# magloop_ad8129.net
KiCad netlist of a schematic drawn in EAGLE
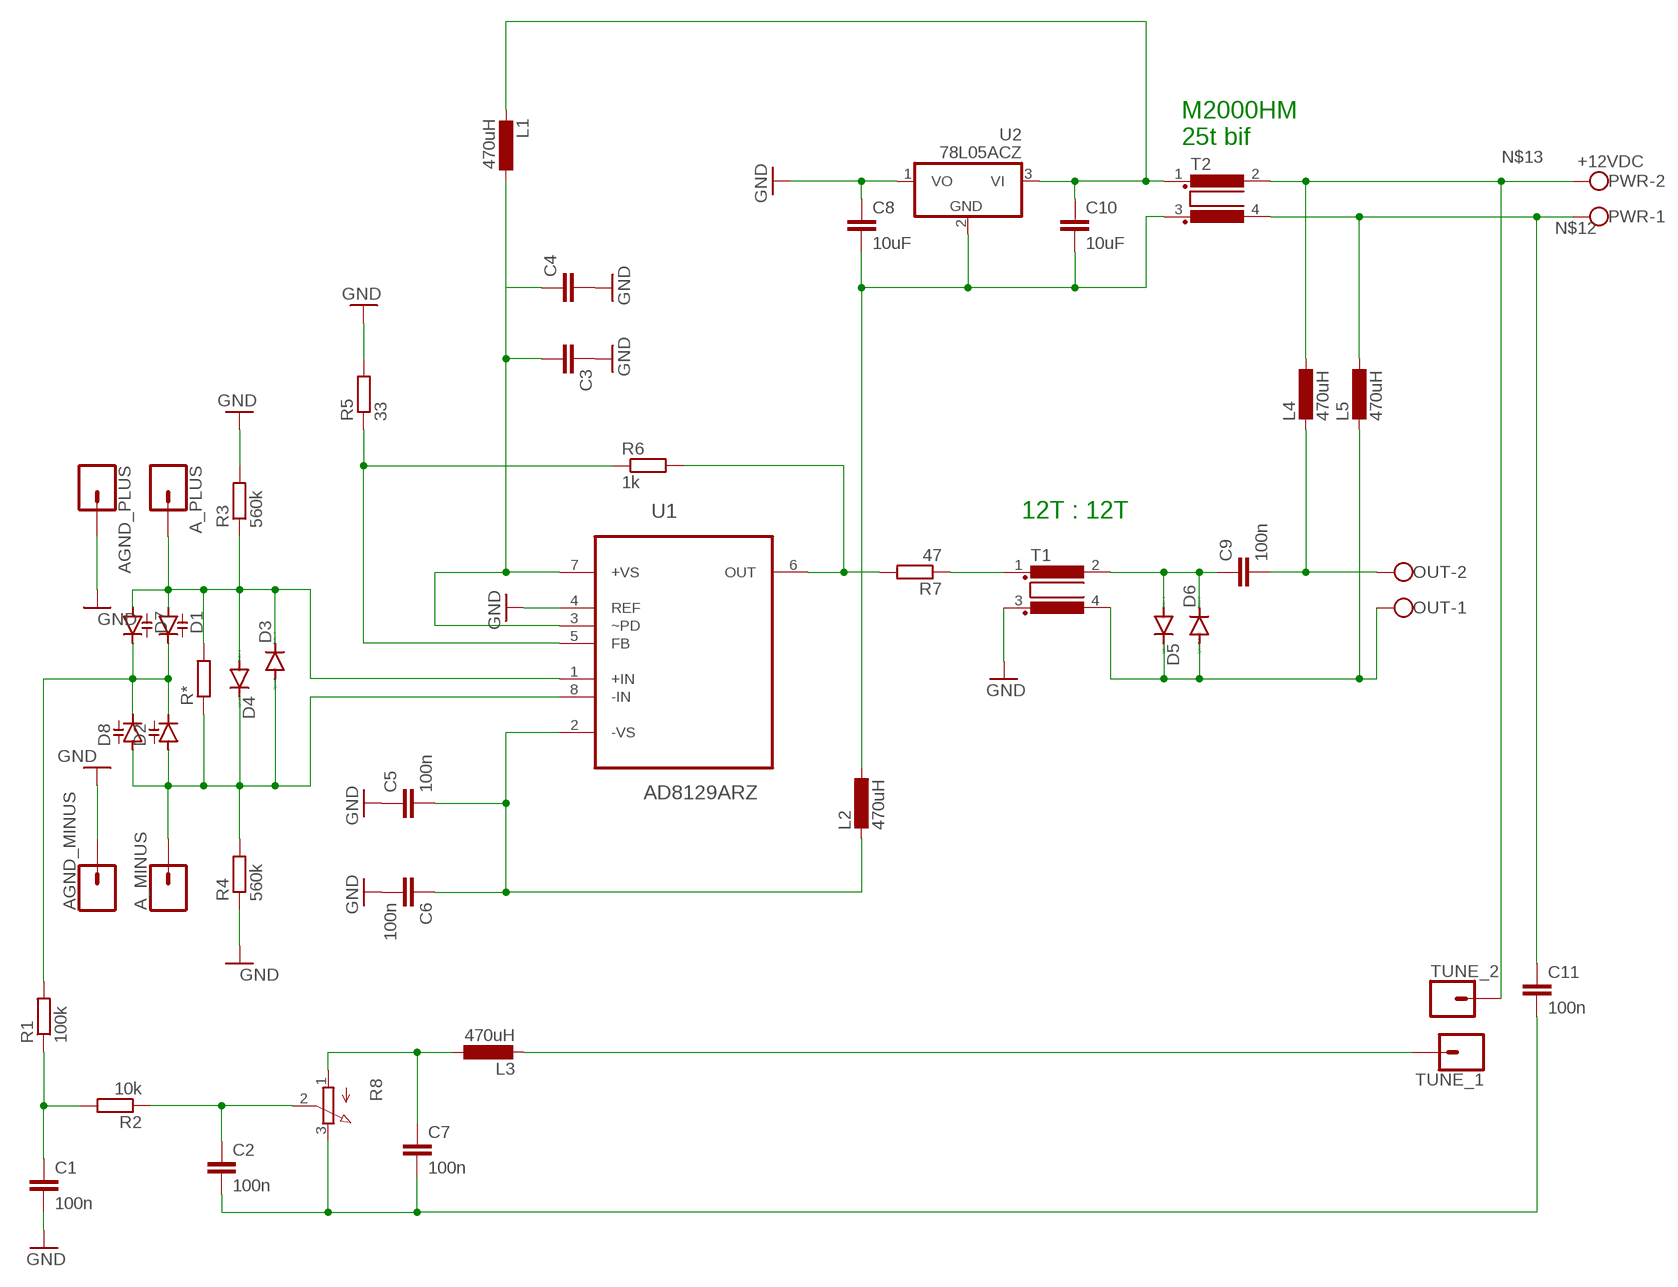
[diagram p0: schematic, sheet 1]

(export (version "E")
  (design (tool "Eeschema 10.0.6"))
  (components
    (comp (ref "AGND_MINUS")
      (value "CONN_01PTH_2MM")
      (footprint "eagle-import:1X01_2MM")
      (libsource (lib "eagle-import") (part "SparkFun-Connectors_CONN_01PTH_2MM"))
    )
    (comp (ref "AGND_PLUS")
      (value "CONN_01PTH_2MM")
      (footprint "eagle-import:1X01_2MM")
      (libsource (lib "eagle-import") (part "SparkFun-Connectors_CONN_01PTH_2MM"))
    )
    (comp (ref "A_MINUS")
      (value "CONN_01PTH_2MM")
      (footprint "eagle-import:1X01_2MM")
      (libsource (lib "eagle-import") (part "CONN_01PTH_2MM"))
    )
    (comp (ref "A_PLUS")
      (value "CONN_01PTH_2MM")
      (footprint "eagle-import:1X01_2MM")
      (libsource (lib "eagle-import") (part "CONN_01PTH_2MM"))
    )
    (comp (ref "C1")
      (value "100n")
      (footprint "eagle-import:C1206")
      (libsource (lib "eagle-import") (part "C-EUC1206"))
    )
    (comp (ref "C2")
      (value "100n")
      (footprint "eagle-import:C1206")
      (libsource (lib "eagle-import") (part "C-EUC1206"))
    )
    (comp (ref "C3")
      (value "C-EUC1206K")
      (footprint "eagle-import:C1206K")
      (libsource (lib "eagle-import") (part "C-EUC1206K"))
    )
    (comp (ref "C4")
      (value "C-EUC1206K")
      (footprint "eagle-import:C1206K")
      (libsource (lib "eagle-import") (part "C-EUC1206K"))
    )
    (comp (ref "C5")
      (value "100n")
      (footprint "eagle-import:C1206K")
      (libsource (lib "eagle-import") (part "C-EUC1206K"))
    )
    (comp (ref "C6")
      (value "100n")
      (footprint "eagle-import:C1206K")
      (libsource (lib "eagle-import") (part "C-EUC1206K"))
    )
    (comp (ref "C7")
      (value "100n")
      (footprint "eagle-import:C1206")
      (libsource (lib "eagle-import") (part "C-EUC1206"))
    )
    (comp (ref "C8")
      (value "10uF")
      (footprint "eagle-import:C1206K")
      (libsource (lib "eagle-import") (part "C-EUC1206K"))
    )
    (comp (ref "C9")
      (value "100n")
      (footprint "eagle-import:C1206")
      (libsource (lib "eagle-import") (part "C-EUC1206"))
    )
    (comp (ref "C10")
      (value "10uF")
      (footprint "eagle-import:C1206K")
      (libsource (lib "eagle-import") (part "C-EUC1206K"))
    )
    (comp (ref "C11")
      (value "100n")
      (footprint "eagle-import:C1206K")
      (libsource (lib "eagle-import") (part "C-EUC1206K"))
    )
    (comp (ref "D1")
      (value "1SV149")
      (footprint "eagle-import:SOT54H")
      (libsource (lib "eagle-import") (part "DIODE_CAPACITANCE-SOT54H"))
    )
    (comp (ref "D2")
      (value "1SV149")
      (footprint "eagle-import:SOT54H")
      (libsource (lib "eagle-import") (part "DIODE_CAPACITANCE-SOT54H"))
    )
    (comp (ref "D3")
      (value "LL4148")
      (footprint "eagle-import:SOD-123_MINI-SMA")
      (libsource (lib "eagle-import") (part "CGRM400-G1"))
    )
    (comp (ref "D4")
      (value "LL4148")
      (footprint "eagle-import:SOD-123_MINI-SMA")
      (libsource (lib "eagle-import") (part "CGRM400-G1"))
    )
    (comp (ref "D5")
      (value "CGRM4001-G")
      (footprint "eagle-import:SOD-123_MINI-SMA")
      (libsource (lib "eagle-import") (part "CGRM400-G1"))
    )
    (comp (ref "D6")
      (value "CGRM4001-G")
      (footprint "eagle-import:SOD-123_MINI-SMA")
      (libsource (lib "eagle-import") (part "CGRM400-G1"))
    )
    (comp (ref "D7")
      (value "1SV149")
      (footprint "eagle-import:SOT54H")
      (libsource (lib "eagle-import") (part "DIODE_CAPACITANCE-SOT54H"))
    )
    (comp (ref "D8")
      (value "1SV149")
      (footprint "eagle-import:SOT54H")
      (libsource (lib "eagle-import") (part "DIODE_CAPACITANCE-SOT54H"))
    )
    (comp (ref "L1")
      (value "470uH")
      (footprint "eagle-import:0207_10")
      (libsource (lib "eagle-import") (part "L-EU0207/10"))
    )
    (comp (ref "L2")
      (value "470uH")
      (footprint "eagle-import:0207_10")
      (libsource (lib "eagle-import") (part "L-EU0207/10"))
    )
    (comp (ref "L3")
      (value "470uH")
      (footprint "eagle-import:0207_10")
      (libsource (lib "eagle-import") (part "L-EU0207/10"))
    )
    (comp (ref "L4")
      (value "470uH")
      (footprint "eagle-import:0207_10")
      (libsource (lib "eagle-import") (part "L-EU0207/10"))
    )
    (comp (ref "L5")
      (value "470uH")
      (footprint "eagle-import:0207_10")
      (libsource (lib "eagle-import") (part "L-EU0207/10"))
    )
    (comp (ref "OUT")
      (value "W237-102")
      (footprint "eagle-import:W237-102")
      (fields (field (name "MPN") "237-102"))
      (libsource (lib "eagle-import") (part "W237-102"))
    )
    (comp (ref "PWR")
      (value "+12VDC")
      (footprint "eagle-import:W237-102")
      (fields (field (name "MPN") "237-102"))
      (libsource (lib "eagle-import") (part "W237-102"))
    )
    (comp (ref "R*")
      (value "R-EU_R1206")
      (footprint "eagle-import:R1206")
      (libsource (lib "eagle-import") (part "R-EU_R1206"))
    )
    (comp (ref "R1")
      (value "100k")
      (footprint "eagle-import:R1206")
      (libsource (lib "eagle-import") (part "R-EU_R1206"))
    )
    (comp (ref "R2")
      (value "10k")
      (footprint "eagle-import:R1206")
      (libsource (lib "eagle-import") (part "R-EU_R1206"))
    )
    (comp (ref "R3")
      (value "560k")
      (footprint "eagle-import:R1206")
      (libsource (lib "eagle-import") (part "R-EU_R1206"))
    )
    (comp (ref "R4")
      (value "560k")
      (footprint "eagle-import:R1206")
      (libsource (lib "eagle-import") (part "R-EU_R1206"))
    )
    (comp (ref "R5")
      (value "33")
      (footprint "eagle-import:R1206")
      (libsource (lib "eagle-import") (part "R-EU_R1206"))
    )
    (comp (ref "R6")
      (value "1k")
      (footprint "eagle-import:R1206")
      (libsource (lib "eagle-import") (part "R-EU_R1206"))
    )
    (comp (ref "R7")
      (value "47")
      (footprint "eagle-import:R1206")
      (libsource (lib "eagle-import") (part "R-EU_R1206"))
    )
    (comp (ref "R8")
      (value "3RP/1610N")
      (footprint "eagle-import:3RP_1610N")
      (libsource (lib "eagle-import") (part "3RP/1610N"))
    )
    (comp (ref "T1")
      (value "R1405UB1/2")
      (footprint "eagle-import:B1_2")
      (libsource (lib "eagle-import") (part "R1405UB1/2"))
    )
    (comp (ref "T2")
      (value "R1405UB1/2")
      (footprint "eagle-import:B1_2")
      (libsource (lib "eagle-import") (part "R1405UB1/2"))
    )
    (comp (ref "TUNE_1")
      (value "CONN_01OFFSET")
      (footprint "eagle-import:1X01_OFFSET")
      (libsource (lib "eagle-import") (part "CONN_01OFFSET"))
    )
    (comp (ref "TUNE_2")
      (value "CONN_01OFFSET")
      (footprint "eagle-import:1X01_OFFSET")
      (libsource (lib "eagle-import") (part "CONN_01OFFSET"))
    )
    (comp (ref "U1")
      (value "AD8129ARZ")
      (footprint "eagle-import:SOIC127P600X175-8N")
      (fields (field (name "MF") "Analog Devices"))
      (libsource (lib "eagle-import") (part "AD8129ARZ"))
    )
    (comp (ref "U2")
      (value "78L05ACZ")
      (footprint "eagle-import:TO-92")
      (fields (field (name "MF") "STMicroelectronics"))
      (libsource (lib "eagle-import") (part "78L05ACZ"))
    )
  )
  (nets
    (net (code "1") (name "/N$12") (class "Default")
      (node (ref "C11") (pin "1") (pinfunction "1_1") (pintype "passive"))
      (node (ref "L5") (pin "1") (pinfunction "1_1") (pintype "passive"))
      (node (ref "PWR") (pin "1") (pinfunction "KL_1") (pintype "passive"))
      (node (ref "T2") (pin "4") (pinfunction "4_4") (pintype "passive"))
    )
    (net (code "2") (name "/N$13") (class "Default")
      (node (ref "L4") (pin "1") (pinfunction "1_1") (pintype "passive"))
      (node (ref "PWR") (pin "2") (pinfunction "KL_2") (pintype "passive"))
      (node (ref "T2") (pin "2") (pinfunction "2_2") (pintype "passive"))
      (node (ref "TUNE_2") (pin "1") (pinfunction "1_1") (pintype "passive"))
    )
    (net (code "3") (name "GND") (class "Default")
      (node (ref "AGND_MINUS") (pin "1") (pinfunction "1_1") (pintype "passive"))
      (node (ref "AGND_PLUS") (pin "1") (pinfunction "1_1") (pintype "passive"))
      (node (ref "C1") (pin "2") (pinfunction "2_2") (pintype "passive"))
      (node (ref "C3") (pin "1") (pinfunction "1_1") (pintype "passive"))
      (node (ref "C4") (pin "2") (pinfunction "2_2") (pintype "passive"))
      (node (ref "C5") (pin "1") (pinfunction "1_1") (pintype "passive"))
      (node (ref "C6") (pin "2") (pinfunction "2_2") (pintype "passive"))
      (node (ref "C8") (pin "1") (pinfunction "1_1") (pintype "passive"))
      (node (ref "R3") (pin "2") (pinfunction "2_2") (pintype "passive"))
      (node (ref "R4") (pin "1") (pinfunction "1_1") (pintype "passive"))
      (node (ref "R5") (pin "2") (pinfunction "2_2") (pintype "passive"))
      (node (ref "T1") (pin "3") (pinfunction "3_3") (pintype "passive"))
      (node (ref "U1") (pin "4") (pinfunction "REF_4") (pintype "input"))
      (node (ref "U2") (pin "1") (pinfunction "VO_1") (pintype "passive"))
    )
    (net (code "4") (name "Net-(C1-Pad1)") (class "Default")
      (node (ref "C1") (pin "1") (pinfunction "1_1") (pintype "passive"))
      (node (ref "R1") (pin "1") (pinfunction "1_1") (pintype "passive"))
      (node (ref "R2") (pin "2") (pinfunction "2_2") (pintype "passive"))
    )
    (net (code "5") (name "Net-(C9-Pad1)") (class "Default")
      (node (ref "C9") (pin "1") (pinfunction "1_1") (pintype "passive"))
      (node (ref "D5") (pin "A") (pinfunction "A_A") (pintype "passive"))
      (node (ref "D6") (pin "C") (pinfunction "C_C") (pintype "passive"))
      (node (ref "T1") (pin "2") (pinfunction "2_2") (pintype "passive"))
    )
    (net (code "6") (name "Net-(D1-PadC)") (class "Default")
      (node (ref "D1") (pin "C") (pinfunction "C_C") (pintype "passive"))
      (node (ref "D2") (pin "C") (pinfunction "C_C") (pintype "passive"))
      (node (ref "D7") (pin "C") (pinfunction "C_C") (pintype "passive"))
      (node (ref "D8") (pin "C") (pinfunction "C_C") (pintype "passive"))
      (node (ref "R1") (pin "2") (pinfunction "2_2") (pintype "passive"))
    )
    (net (code "7") (name "Net-(L3-Pad2)") (class "Default")
      (node (ref "L3") (pin "2") (pinfunction "2_2") (pintype "passive"))
      (node (ref "TUNE_1") (pin "1") (pinfunction "1_1") (pintype "passive"))
    )
    (net (code "8") (name "Net-(OUTA-KL)") (class "Default")
      (node (ref "D5") (pin "C") (pinfunction "C_C") (pintype "passive"))
      (node (ref "D6") (pin "A") (pinfunction "A_A") (pintype "passive"))
      (node (ref "L5") (pin "2") (pinfunction "2_2") (pintype "passive"))
      (node (ref "OUT") (pin "1") (pinfunction "KL_1") (pintype "passive"))
      (node (ref "T1") (pin "4") (pinfunction "4_4") (pintype "passive"))
    )
    (net (code "9") (name "Net-(OUTB-KL)") (class "Default")
      (node (ref "C9") (pin "2") (pinfunction "2_2") (pintype "passive"))
      (node (ref "L4") (pin "2") (pinfunction "2_2") (pintype "passive"))
      (node (ref "OUT") (pin "2") (pinfunction "KL_2") (pintype "passive"))
    )
    (net (code "10") (name "Net-(R7-Pad1)") (class "Default")
      (node (ref "R7") (pin "1") (pinfunction "1_1") (pintype "passive"))
      (node (ref "T1") (pin "1") (pinfunction "1_1") (pintype "passive"))
    )
    (net (code "11") (name "Net-(R8-A)") (class "Default")
      (node (ref "C7") (pin "1") (pinfunction "1_1") (pintype "passive"))
      (node (ref "L3") (pin "1") (pinfunction "1_1") (pintype "passive"))
      (node (ref "R8") (pin "1") (pinfunction "A_1") (pintype "passive"))
    )
    (net (code "12") (name "Net-(R8-E)") (class "Default")
      (node (ref "C11") (pin "2") (pinfunction "2_2") (pintype "passive"))
      (node (ref "C2") (pin "2") (pinfunction "2_2") (pintype "passive"))
      (node (ref "C7") (pin "2") (pinfunction "2_2") (pintype "passive"))
      (node (ref "R8") (pin "3") (pinfunction "E_3") (pintype "passive"))
    )
    (net (code "13") (name "Net-(R8-S)") (class "Default")
      (node (ref "C2") (pin "1") (pinfunction "1_1") (pintype "passive"))
      (node (ref "R2") (pin "1") (pinfunction "1_1") (pintype "passive"))
      (node (ref "R8") (pin "2") (pinfunction "S_2") (pintype "passive"))
    )
    (net (code "14") (name "Net-(U1-+IN)") (class "Default")
      (node (ref "A_PLUS") (pin "1") (pinfunction "1_1") (pintype "passive"))
      (node (ref "D1") (pin "A") (pinfunction "A_A") (pintype "passive"))
      (node (ref "D3") (pin "C") (pinfunction "C_C") (pintype "passive"))
      (node (ref "D4") (pin "A") (pinfunction "A_A") (pintype "passive"))
      (node (ref "D7") (pin "A") (pinfunction "A_A") (pintype "passive"))
      (node (ref "R*") (pin "2") (pinfunction "2_2") (pintype "passive"))
      (node (ref "R3") (pin "1") (pinfunction "1_1") (pintype "passive"))
      (node (ref "U1") (pin "1") (pinfunction "+IN_1") (pintype "input"))
    )
    (net (code "15") (name "Net-(U1-+VS)") (class "Default")
      (node (ref "C3") (pin "2") (pinfunction "2_2") (pintype "passive"))
      (node (ref "C4") (pin "1") (pinfunction "1_1") (pintype "passive"))
      (node (ref "L1") (pin "1") (pinfunction "1_1") (pintype "passive"))
      (node (ref "U1") (pin "3") (pinfunction "~{PD}_3") (pintype "passive"))
      (node (ref "U1") (pin "7") (pinfunction "+VS_7") (pintype "power_in"))
    )
    (net (code "16") (name "Net-(U1--IN)") (class "Default")
      (node (ref "A_MINUS") (pin "1") (pinfunction "1_1") (pintype "passive"))
      (node (ref "D2") (pin "A") (pinfunction "A_A") (pintype "passive"))
      (node (ref "D3") (pin "A") (pinfunction "A_A") (pintype "passive"))
      (node (ref "D4") (pin "C") (pinfunction "C_C") (pintype "passive"))
      (node (ref "D8") (pin "A") (pinfunction "A_A") (pintype "passive"))
      (node (ref "R*") (pin "1") (pinfunction "1_1") (pintype "passive"))
      (node (ref "R4") (pin "2") (pinfunction "2_2") (pintype "passive"))
      (node (ref "U1") (pin "8") (pinfunction "-IN_8") (pintype "input"))
    )
    (net (code "17") (name "Net-(U1--VS)") (class "Default")
      (node (ref "C5") (pin "2") (pinfunction "2_2") (pintype "passive"))
      (node (ref "C6") (pin "1") (pinfunction "1_1") (pintype "passive"))
      (node (ref "L2") (pin "2") (pinfunction "2_2") (pintype "passive"))
      (node (ref "U1") (pin "2") (pinfunction "-VS_2") (pintype "power_in"))
    )
    (net (code "18") (name "Net-(U1-FB)") (class "Default")
      (node (ref "R5") (pin "1") (pinfunction "1_1") (pintype "passive"))
      (node (ref "R6") (pin "1") (pinfunction "1_1") (pintype "passive"))
      (node (ref "U1") (pin "5") (pinfunction "FB_5") (pintype "input"))
    )
    (net (code "19") (name "Net-(U1-OUT)") (class "Default")
      (node (ref "R6") (pin "2") (pinfunction "2_2") (pintype "passive"))
      (node (ref "R7") (pin "2") (pinfunction "2_2") (pintype "passive"))
      (node (ref "U1") (pin "6") (pinfunction "OUT_6") (pintype "output"))
    )
    (net (code "20") (name "Net-(U2-GND)") (class "Default")
      (node (ref "C10") (pin "2") (pinfunction "2_2") (pintype "passive"))
      (node (ref "C8") (pin "2") (pinfunction "2_2") (pintype "passive"))
      (node (ref "L2") (pin "1") (pinfunction "1_1") (pintype "passive"))
      (node (ref "T2") (pin "3") (pinfunction "3_3") (pintype "passive"))
      (node (ref "U2") (pin "2") (pinfunction "GND_2") (pintype "passive"))
    )
    (net (code "21") (name "Net-(U2-VI)") (class "Default")
      (node (ref "C10") (pin "1") (pinfunction "1_1") (pintype "passive"))
      (node (ref "L1") (pin "2") (pinfunction "2_2") (pintype "passive"))
      (node (ref "T2") (pin "1") (pinfunction "1_1") (pintype "passive"))
      (node (ref "U2") (pin "3") (pinfunction "VI_3") (pintype "input"))
    )
  )
)
